# a406-4069-overdrive.net
KiCad netlist of a schematic drawn in EAGLE
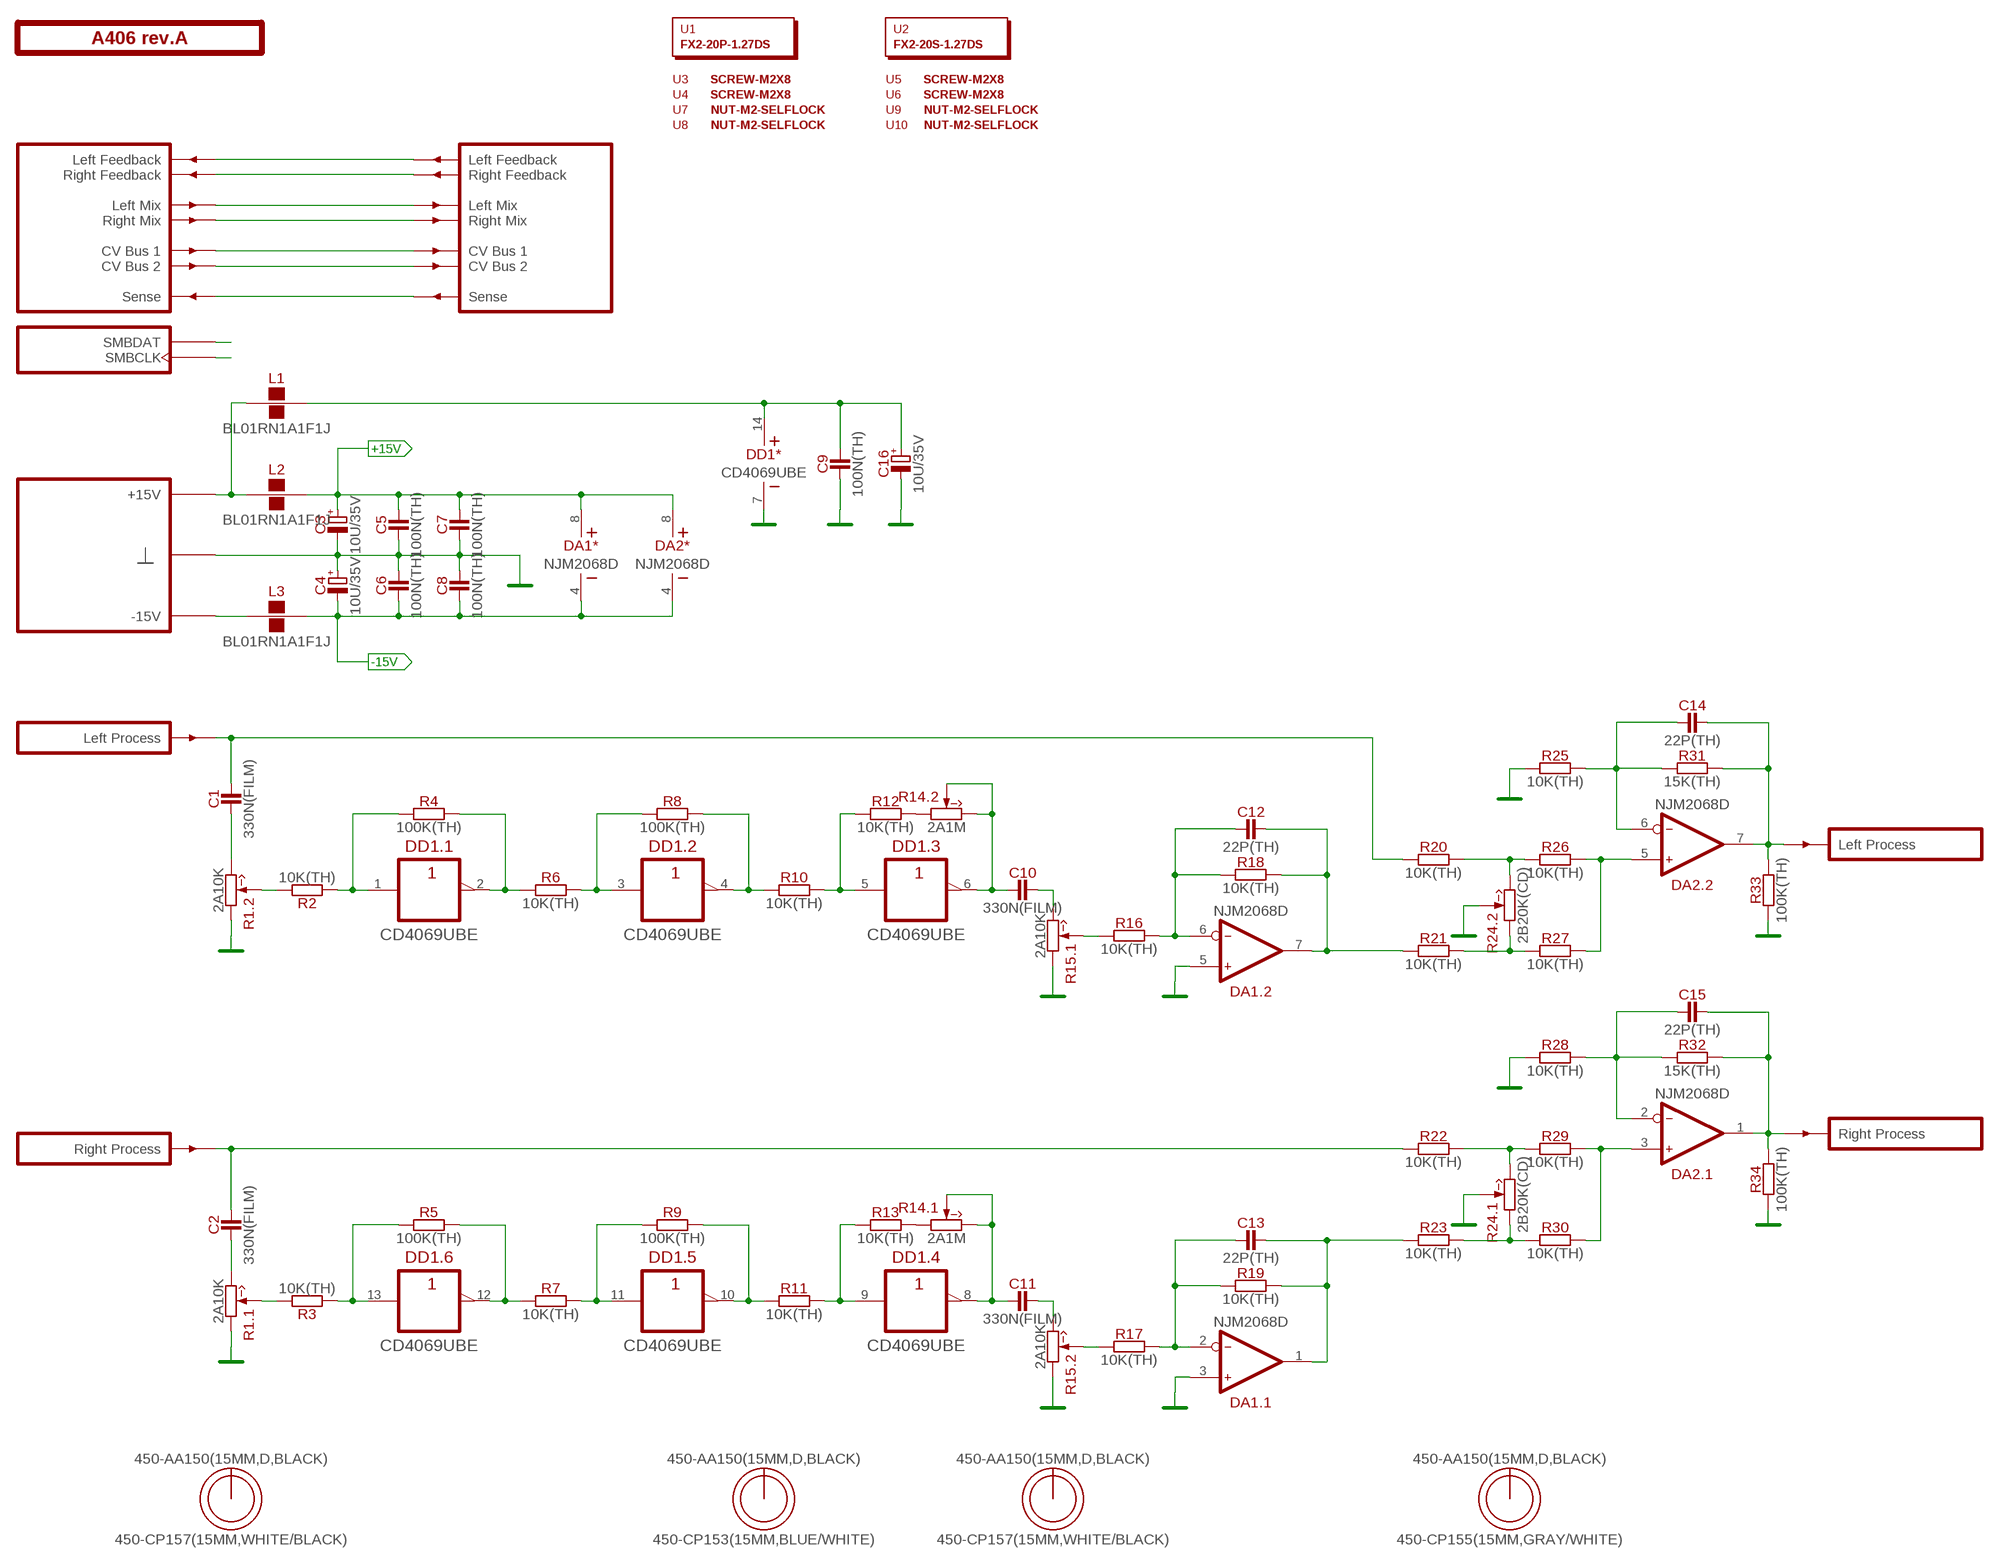
[diagram p0: schematic, sheet 1]

(export (version "E")
  (design (tool "Eeschema 10.0.6"))
  (components
    (comp (ref "C1")
      (value "330N(FILM)")
      (footprint "eagle-import:C050-035X075")
      (libsource (lib "eagle-import") (part "?330N(FILM)"))
    )
    (comp (ref "C2")
      (value "330N(FILM)")
      (footprint "eagle-import:C050-035X075")
      (libsource (lib "eagle-import") (part "?330N(FILM)"))
    )
    (comp (ref "C3")
      (value "10U/35V")
      (footprint "eagle-import:E2-5")
      (libsource (lib "eagle-import") (part "?10U/35V"))
    )
    (comp (ref "C4")
      (value "10U/35V")
      (footprint "eagle-import:E2-5")
      (libsource (lib "eagle-import") (part "?10U/35V"))
    )
    (comp (ref "C5")
      (value "100N(TH)")
      (footprint "eagle-import:C050-024X044")
      (libsource (lib "eagle-import") (part "?100N(TH)"))
    )
    (comp (ref "C6")
      (value "100N(TH)")
      (footprint "eagle-import:C050-024X044")
      (libsource (lib "eagle-import") (part "?100N(TH)"))
    )
    (comp (ref "C7")
      (value "100N(TH)")
      (footprint "eagle-import:C050-024X044")
      (libsource (lib "eagle-import") (part "?100N(TH)"))
    )
    (comp (ref "C8")
      (value "100N(TH)")
      (footprint "eagle-import:C050-024X044")
      (libsource (lib "eagle-import") (part "?100N(TH)"))
    )
    (comp (ref "C9")
      (value "100N(TH)")
      (footprint "eagle-import:C050-024X044")
      (libsource (lib "eagle-import") (part "?100N(TH)"))
    )
    (comp (ref "C10")
      (value "330N(FILM)")
      (footprint "eagle-import:C050-035X075")
      (libsource (lib "eagle-import") (part "?330N(FILM)"))
    )
    (comp (ref "C11")
      (value "330N(FILM)")
      (footprint "eagle-import:C050-035X075")
      (libsource (lib "eagle-import") (part "?330N(FILM)"))
    )
    (comp (ref "C12")
      (value "22P(TH)")
      (footprint "eagle-import:C050-024X044")
      (libsource (lib "eagle-import") (part "?22P(TH)"))
    )
    (comp (ref "C13")
      (value "22P(TH)")
      (footprint "eagle-import:C050-024X044")
      (libsource (lib "eagle-import") (part "?22P(TH)"))
    )
    (comp (ref "C14")
      (value "22P(TH)")
      (footprint "eagle-import:C050-024X044")
      (libsource (lib "eagle-import") (part "?22P(TH)"))
    )
    (comp (ref "C15")
      (value "22P(TH)")
      (footprint "eagle-import:C050-024X044")
      (libsource (lib "eagle-import") (part "?22P(TH)"))
    )
    (comp (ref "C16")
      (value "10U/35V")
      (footprint "eagle-import:E2-5")
      (libsource (lib "eagle-import") (part "?10U/35V"))
    )
    (comp (ref "DA1")
      (value "NJM2068D")
      (footprint "eagle-import:DIP-8")
      (libsource (lib "eagle-import") (part "NJM2068D"))
    )
    (comp (ref "DA2")
      (value "NJM2068D")
      (footprint "eagle-import:DIP-8")
      (libsource (lib "eagle-import") (part "NJM2068D"))
    )
    (comp (ref "DD1")
      (value "CD4069UBE")
      (footprint "eagle-import:DIP-14")
      (libsource (lib "eagle-import") (part "CD4069UBE"))
    )
    (comp (ref "L1")
      (value "BL01RN1A1F1J")
      (footprint "eagle-import:BL01RN1A")
      (libsource (lib "eagle-import") (part "BL01RN1A?1F1J"))
    )
    (comp (ref "L2")
      (value "BL01RN1A1F1J")
      (footprint "eagle-import:BL01RN1A")
      (libsource (lib "eagle-import") (part "BL01RN1A?1F1J"))
    )
    (comp (ref "L3")
      (value "BL01RN1A1F1J")
      (footprint "eagle-import:BL01RN1A")
      (libsource (lib "eagle-import") (part "BL01RN1A?1F1J"))
    )
    (comp (ref "O2")
      (value "450-AA150(15MM,D,BLACK)")
      (footprint "eagle-import:EMPTY")
      (libsource (lib "eagle-import") (part "450-AA?150(15MM,D,BLACK)"))
    )
    (comp (ref "O3")
      (value "450-CP157(15MM,WHITE/BLACK)")
      (footprint "eagle-import:EMPTY")
      (libsource (lib "eagle-import") (part "450-C?P157(15MM,WHITE/BLACK)"))
    )
    (comp (ref "O4")
      (value "450-AA150(15MM,D,BLACK)")
      (footprint "eagle-import:EMPTY")
      (libsource (lib "eagle-import") (part "450-AA?150(15MM,D,BLACK)"))
    )
    (comp (ref "O5")
      (value "450-CP153(15MM,BLUE/WHITE)")
      (footprint "eagle-import:EMPTY")
      (libsource (lib "eagle-import") (part "450-C?P153(15MM,BLUE/WHITE)"))
    )
    (comp (ref "O6")
      (value "450-AA150(15MM,D,BLACK)")
      (footprint "eagle-import:EMPTY")
      (libsource (lib "eagle-import") (part "450-AA?150(15MM,D,BLACK)"))
    )
    (comp (ref "O7")
      (value "450-CP157(15MM,WHITE/BLACK)")
      (footprint "eagle-import:EMPTY")
      (libsource (lib "eagle-import") (part "450-C?P157(15MM,WHITE/BLACK)"))
    )
    (comp (ref "O8")
      (value "450-AA150(15MM,D,BLACK)")
      (footprint "eagle-import:EMPTY")
      (libsource (lib "eagle-import") (part "450-AA?150(15MM,D,BLACK)"))
    )
    (comp (ref "O9")
      (value "450-CP155(15MM,GRAY/WHITE)")
      (footprint "eagle-import:EMPTY")
      (libsource (lib "eagle-import") (part "450-C?P155(15MM,GRAY/WHITE)"))
    )
    (comp (ref "PCB1")
      (value "A406 rev.A")
      (footprint "eagle-import:ST2-BOARD-50")
      (libsource (lib "eagle-import") (part "ST2-BOARD-?50"))
    )
    (comp (ref "R1")
      (value "2A10K")
      (footprint "eagle-import:RV11-DUAL")
      (libsource (lib "eagle-import") (part "2?A10K"))
    )
    (comp (ref "R2")
      (value "10K(TH)")
      (footprint "eagle-import:R-0207_10")
      (libsource (lib "eagle-import") (part "?10K(TH)"))
    )
    (comp (ref "R3")
      (value "10K(TH)")
      (footprint "eagle-import:R-0207_10")
      (libsource (lib "eagle-import") (part "?10K(TH)"))
    )
    (comp (ref "R4")
      (value "100K(TH)")
      (footprint "eagle-import:R-0207_10")
      (libsource (lib "eagle-import") (part "?100K(TH)"))
    )
    (comp (ref "R5")
      (value "100K(TH)")
      (footprint "eagle-import:R-0207_10")
      (libsource (lib "eagle-import") (part "?100K(TH)"))
    )
    (comp (ref "R6")
      (value "10K(TH)")
      (footprint "eagle-import:R-0207_10")
      (libsource (lib "eagle-import") (part "?10K(TH)"))
    )
    (comp (ref "R7")
      (value "10K(TH)")
      (footprint "eagle-import:R-0207_10")
      (libsource (lib "eagle-import") (part "?10K(TH)"))
    )
    (comp (ref "R8")
      (value "100K(TH)")
      (footprint "eagle-import:R-0207_10")
      (libsource (lib "eagle-import") (part "?100K(TH)"))
    )
    (comp (ref "R9")
      (value "100K(TH)")
      (footprint "eagle-import:R-0207_10")
      (libsource (lib "eagle-import") (part "?100K(TH)"))
    )
    (comp (ref "R10")
      (value "10K(TH)")
      (footprint "eagle-import:R-0207_10")
      (libsource (lib "eagle-import") (part "?10K(TH)"))
    )
    (comp (ref "R11")
      (value "10K(TH)")
      (footprint "eagle-import:R-0207_10")
      (libsource (lib "eagle-import") (part "?10K(TH)"))
    )
    (comp (ref "R12")
      (value "10K(TH)")
      (footprint "eagle-import:R-0207_10")
      (libsource (lib "eagle-import") (part "?10K(TH)"))
    )
    (comp (ref "R13")
      (value "10K(TH)")
      (footprint "eagle-import:R-0207_10")
      (libsource (lib "eagle-import") (part "?10K(TH)"))
    )
    (comp (ref "R14")
      (value "2A1M")
      (footprint "eagle-import:RV11-DUAL")
      (libsource (lib "eagle-import") (part "2?A1M"))
    )
    (comp (ref "R15")
      (value "2A10K")
      (footprint "eagle-import:RV11-DUAL")
      (libsource (lib "eagle-import") (part "2?A10K"))
    )
    (comp (ref "R16")
      (value "10K(TH)")
      (footprint "eagle-import:R-0207_10")
      (libsource (lib "eagle-import") (part "?10K(TH)"))
    )
    (comp (ref "R17")
      (value "10K(TH)")
      (footprint "eagle-import:R-0207_10")
      (libsource (lib "eagle-import") (part "?10K(TH)"))
    )
    (comp (ref "R18")
      (value "10K(TH)")
      (footprint "eagle-import:R-0207_10")
      (libsource (lib "eagle-import") (part "?10K(TH)"))
    )
    (comp (ref "R19")
      (value "10K(TH)")
      (footprint "eagle-import:R-0207_10")
      (libsource (lib "eagle-import") (part "?10K(TH)"))
    )
    (comp (ref "R20")
      (value "10K(TH)")
      (footprint "eagle-import:R-0207_10")
      (libsource (lib "eagle-import") (part "?10K(TH)"))
    )
    (comp (ref "R21")
      (value "10K(TH)")
      (footprint "eagle-import:R-0207_10")
      (libsource (lib "eagle-import") (part "?10K(TH)"))
    )
    (comp (ref "R22")
      (value "10K(TH)")
      (footprint "eagle-import:R-0207_10")
      (libsource (lib "eagle-import") (part "?10K(TH)"))
    )
    (comp (ref "R23")
      (value "10K(TH)")
      (footprint "eagle-import:R-0207_10")
      (libsource (lib "eagle-import") (part "?10K(TH)"))
    )
    (comp (ref "R24")
      (value "2B20K(CD)")
      (footprint "eagle-import:RV11-DUAL")
      (libsource (lib "eagle-import") (part "2?B20K(CD)"))
    )
    (comp (ref "R25")
      (value "10K(TH)")
      (footprint "eagle-import:R-0207_10")
      (libsource (lib "eagle-import") (part "?10K(TH)"))
    )
    (comp (ref "R26")
      (value "10K(TH)")
      (footprint "eagle-import:R-0207_10")
      (libsource (lib "eagle-import") (part "?10K(TH)"))
    )
    (comp (ref "R27")
      (value "10K(TH)")
      (footprint "eagle-import:R-0207_10")
      (libsource (lib "eagle-import") (part "?10K(TH)"))
    )
    (comp (ref "R28")
      (value "10K(TH)")
      (footprint "eagle-import:R-0207_10")
      (libsource (lib "eagle-import") (part "?10K(TH)"))
    )
    (comp (ref "R29")
      (value "10K(TH)")
      (footprint "eagle-import:R-0207_10")
      (libsource (lib "eagle-import") (part "?10K(TH)"))
    )
    (comp (ref "R30")
      (value "10K(TH)")
      (footprint "eagle-import:R-0207_10")
      (libsource (lib "eagle-import") (part "?10K(TH)"))
    )
    (comp (ref "R31")
      (value "15K(TH)")
      (footprint "eagle-import:R-0207_10")
      (libsource (lib "eagle-import") (part "?15K(TH)"))
    )
    (comp (ref "R32")
      (value "15K(TH)")
      (footprint "eagle-import:R-0207_10")
      (libsource (lib "eagle-import") (part "?15K(TH)"))
    )
    (comp (ref "R33")
      (value "100K(TH)")
      (footprint "eagle-import:R-0207_10")
      (libsource (lib "eagle-import") (part "?100K(TH)"))
    )
    (comp (ref "R34")
      (value "100K(TH)")
      (footprint "eagle-import:R-0207_10")
      (libsource (lib "eagle-import") (part "?100K(TH)"))
    )
    (comp (ref "U1")
      (value "FX2-20P-1.27DS")
      (footprint "eagle-import:EMPTY")
      (libsource (lib "eagle-import") (part "?FX2-20P-1.27DS"))
    )
    (comp (ref "U2")
      (value "FX2-20S-1.27DS")
      (footprint "eagle-import:EMPTY")
      (libsource (lib "eagle-import") (part "?FX2-20S-1.27DS"))
    )
    (comp (ref "U3")
      (value "SCREW-M2X8")
      (footprint "eagle-import:EMPTY")
      (libsource (lib "eagle-import") (part "?SCREW-M2X8"))
    )
    (comp (ref "U4")
      (value "SCREW-M2X8")
      (footprint "eagle-import:EMPTY")
      (libsource (lib "eagle-import") (part "?SCREW-M2X8"))
    )
    (comp (ref "U5")
      (value "SCREW-M2X8")
      (footprint "eagle-import:EMPTY")
      (libsource (lib "eagle-import") (part "?SCREW-M2X8"))
    )
    (comp (ref "U6")
      (value "SCREW-M2X8")
      (footprint "eagle-import:EMPTY")
      (libsource (lib "eagle-import") (part "?SCREW-M2X8"))
    )
    (comp (ref "U7")
      (value "NUT-M2-SELFLOCK")
      (footprint "eagle-import:EMPTY")
      (libsource (lib "eagle-import") (part "?NUT-M2-SELFLOCK"))
    )
    (comp (ref "U8")
      (value "NUT-M2-SELFLOCK")
      (footprint "eagle-import:EMPTY")
      (libsource (lib "eagle-import") (part "?NUT-M2-SELFLOCK"))
    )
    (comp (ref "U9")
      (value "NUT-M2-SELFLOCK")
      (footprint "eagle-import:EMPTY")
      (libsource (lib "eagle-import") (part "?NUT-M2-SELFLOCK"))
    )
    (comp (ref "U10")
      (value "NUT-M2-SELFLOCK")
      (footprint "eagle-import:EMPTY")
      (libsource (lib "eagle-import") (part "?NUT-M2-SELFLOCK"))
    )
  )
  (nets
    (net (code "1") (name "+15V") (class "Default")
      (node (ref "C3") (pin "+") (pinfunction "+_+") (pintype "passive"))
      (node (ref "C5") (pin "2") (pinfunction "2_2") (pintype "passive"))
      (node (ref "C7") (pin "2") (pinfunction "2_2") (pintype "passive"))
      (node (ref "DA1") (pin "8") (pinfunction "V+_8") (pintype "power_in"))
      (node (ref "DA2") (pin "8") (pinfunction "V+_8") (pintype "power_in"))
      (node (ref "L2") (pin "2") (pinfunction "2_2") (pintype "passive"))
    )
    (net (code "2") (name "-15V") (class "Default")
      (node (ref "C4") (pin "-") (pinfunction "-_-") (pintype "passive"))
      (node (ref "C6") (pin "1") (pinfunction "1_1") (pintype "passive"))
      (node (ref "C8") (pin "1") (pinfunction "1_1") (pintype "passive"))
      (node (ref "DA1") (pin "4") (pinfunction "V-_4") (pintype "power_in"))
      (node (ref "DA2") (pin "4") (pinfunction "V-_4") (pintype "power_in"))
      (node (ref "L3") (pin "2") (pinfunction "2_2") (pintype "passive"))
    )
    (net (code "3") (name "GND") (class "Default")
      (node (ref "C16") (pin "-") (pinfunction "-_-") (pintype "passive"))
      (node (ref "C3") (pin "-") (pinfunction "-_-") (pintype "passive"))
      (node (ref "C4") (pin "+") (pinfunction "+_+") (pintype "passive"))
      (node (ref "C5") (pin "1") (pinfunction "1_1") (pintype "passive"))
      (node (ref "C6") (pin "2") (pinfunction "2_2") (pintype "passive"))
      (node (ref "C7") (pin "1") (pinfunction "1_1") (pintype "passive"))
      (node (ref "C8") (pin "2") (pinfunction "2_2") (pintype "passive"))
      (node (ref "C9") (pin "1") (pinfunction "1_1") (pintype "passive"))
      (node (ref "DA1") (pin "3") (pinfunction "IN+_3") (pintype "input"))
      (node (ref "DA1") (pin "5") (pinfunction "IN+_5") (pintype "input"))
      (node (ref "DD1") (pin "7") (pinfunction "V-_7") (pintype "power_in"))
      (node (ref "PCB1") (pin "B4") (pinfunction "GND_B4") (pintype "bidirectional"))
      (node (ref "PCB1") (pin "B4'") (pinfunction "GND_B4'") (pintype "bidirectional"))
      (node (ref "PCB1") (pin "B5") (pinfunction "GND_B5") (pintype "bidirectional"))
      (node (ref "PCB1") (pin "B5'") (pinfunction "GND_B5'") (pintype "bidirectional"))
      (node (ref "PCB1") (pin "B6") (pinfunction "GND_B6") (pintype "bidirectional"))
      (node (ref "PCB1") (pin "B6'") (pinfunction "GND_B6'") (pintype "bidirectional"))
      (node (ref "PCB1") (pin "B7") (pinfunction "GND_B7") (pintype "bidirectional"))
      (node (ref "PCB1") (pin "B7'") (pinfunction "GND_B7'") (pintype "bidirectional"))
      (node (ref "PCB1") (pin "B8") (pinfunction "GND_B8") (pintype "bidirectional"))
      (node (ref "PCB1") (pin "B8'") (pinfunction "GND_B8'") (pintype "bidirectional"))
      (node (ref "R1") (pin "1") (pinfunction "CCW_1") (pintype "passive"))
      (node (ref "R1") (pin "1'") (pinfunction "CCW_1'") (pintype "passive"))
      (node (ref "R15") (pin "1") (pinfunction "CCW_1") (pintype "passive"))
      (node (ref "R15") (pin "1'") (pinfunction "CCW_1'") (pintype "passive"))
      (node (ref "R24") (pin "2") (pinfunction "W_2") (pintype "passive"))
      (node (ref "R24") (pin "2'") (pinfunction "W_2'") (pintype "passive"))
      (node (ref "R25") (pin "1") (pinfunction "1_1") (pintype "passive"))
      (node (ref "R28") (pin "1") (pinfunction "1_1") (pintype "passive"))
      (node (ref "R33") (pin "1") (pinfunction "1_1") (pintype "passive"))
      (node (ref "R34") (pin "1") (pinfunction "1_1") (pintype "passive"))
    )
    (net (code "4") (name "Net-(DA1B-IN-)") (class "Default")
      (node (ref "C13") (pin "1") (pinfunction "1_1") (pintype "passive"))
      (node (ref "DA1") (pin "2") (pinfunction "IN-_2") (pintype "input"))
      (node (ref "R17") (pin "2") (pinfunction "2_2") (pintype "passive"))
      (node (ref "R19") (pin "1") (pinfunction "1_1") (pintype "passive"))
    )
    (net (code "5") (name "Net-(DA1B-OUT)") (class "Default")
      (node (ref "C13") (pin "2") (pinfunction "2_2") (pintype "passive"))
      (node (ref "DA1") (pin "1") (pinfunction "OUT_1") (pintype "output"))
      (node (ref "R19") (pin "2") (pinfunction "2_2") (pintype "passive"))
      (node (ref "R23") (pin "1") (pinfunction "1_1") (pintype "passive"))
    )
    (net (code "6") (name "Net-(DA1C-IN-)") (class "Default")
      (node (ref "C12") (pin "1") (pinfunction "1_1") (pintype "passive"))
      (node (ref "DA1") (pin "6") (pinfunction "IN-_6") (pintype "input"))
      (node (ref "R16") (pin "2") (pinfunction "2_2") (pintype "passive"))
      (node (ref "R18") (pin "1") (pinfunction "1_1") (pintype "passive"))
    )
    (net (code "7") (name "Net-(DA1C-OUT)") (class "Default")
      (node (ref "C12") (pin "2") (pinfunction "2_2") (pintype "passive"))
      (node (ref "DA1") (pin "7") (pinfunction "OUT_7") (pintype "output"))
      (node (ref "R18") (pin "2") (pinfunction "2_2") (pintype "passive"))
      (node (ref "R21") (pin "1") (pinfunction "1_1") (pintype "passive"))
    )
    (net (code "8") (name "Net-(DA2B-IN+)") (class "Default")
      (node (ref "DA2") (pin "3") (pinfunction "IN+_3") (pintype "input"))
      (node (ref "R29") (pin "2") (pinfunction "2_2") (pintype "passive"))
      (node (ref "R30") (pin "2") (pinfunction "2_2") (pintype "passive"))
    )
    (net (code "9") (name "Net-(DA2B-IN-)") (class "Default")
      (node (ref "C15") (pin "1") (pinfunction "1_1") (pintype "passive"))
      (node (ref "DA2") (pin "2") (pinfunction "IN-_2") (pintype "input"))
      (node (ref "R28") (pin "2") (pinfunction "2_2") (pintype "passive"))
      (node (ref "R32") (pin "1") (pinfunction "1_1") (pintype "passive"))
    )
    (net (code "10") (name "Net-(DA2B-OUT)") (class "Default")
      (node (ref "C15") (pin "2") (pinfunction "2_2") (pintype "passive"))
      (node (ref "DA2") (pin "1") (pinfunction "OUT_1") (pintype "output"))
      (node (ref "PCB1") (pin "BOUTR'") (pinfunction "OUTR_BOUTR'") (pintype "bidirectional"))
      (node (ref "R32") (pin "2") (pinfunction "2_2") (pintype "passive"))
      (node (ref "R34") (pin "2") (pinfunction "2_2") (pintype "passive"))
    )
    (net (code "11") (name "Net-(DA2C-IN+)") (class "Default")
      (node (ref "DA2") (pin "5") (pinfunction "IN+_5") (pintype "input"))
      (node (ref "R26") (pin "2") (pinfunction "2_2") (pintype "passive"))
      (node (ref "R27") (pin "2") (pinfunction "2_2") (pintype "passive"))
    )
    (net (code "12") (name "Net-(DA2C-IN-)") (class "Default")
      (node (ref "C14") (pin "1") (pinfunction "1_1") (pintype "passive"))
      (node (ref "DA2") (pin "6") (pinfunction "IN-_6") (pintype "input"))
      (node (ref "R25") (pin "2") (pinfunction "2_2") (pintype "passive"))
      (node (ref "R31") (pin "1") (pinfunction "1_1") (pintype "passive"))
    )
    (net (code "13") (name "Net-(DA2C-OUT)") (class "Default")
      (node (ref "C14") (pin "2") (pinfunction "2_2") (pintype "passive"))
      (node (ref "DA2") (pin "7") (pinfunction "OUT_7") (pintype "output"))
      (node (ref "PCB1") (pin "BOUTL'") (pinfunction "OUTL_BOUTL'") (pintype "bidirectional"))
      (node (ref "R31") (pin "2") (pinfunction "2_2") (pintype "passive"))
      (node (ref "R33") (pin "2") (pinfunction "2_2") (pintype "passive"))
    )
    (net (code "14") (name "Net-(DD1A-V+)") (class "Default")
      (node (ref "C16") (pin "+") (pinfunction "+_+") (pintype "passive"))
      (node (ref "C9") (pin "2") (pinfunction "2_2") (pintype "passive"))
      (node (ref "DD1") (pin "14") (pinfunction "V+_14") (pintype "power_in"))
      (node (ref "L1") (pin "2") (pinfunction "2_2") (pintype "passive"))
    )
    (net (code "15") (name "Net-(DD1B-A)") (class "Default")
      (node (ref "DD1") (pin "1") (pinfunction "A_1") (pintype "input"))
      (node (ref "R2") (pin "1") (pinfunction "1_1") (pintype "passive"))
      (node (ref "R4") (pin "1") (pinfunction "1_1") (pintype "passive"))
    )
    (net (code "16") (name "Net-(DD1B-Y)") (class "Default")
      (node (ref "DD1") (pin "2") (pinfunction "Y_2") (pintype "output"))
      (node (ref "R4") (pin "2") (pinfunction "2_2") (pintype "passive"))
      (node (ref "R6") (pin "1") (pinfunction "1_1") (pintype "passive"))
    )
    (net (code "17") (name "Net-(DD1C-A)") (class "Default")
      (node (ref "DD1") (pin "3") (pinfunction "A_3") (pintype "input"))
      (node (ref "R6") (pin "2") (pinfunction "2_2") (pintype "passive"))
      (node (ref "R8") (pin "1") (pinfunction "1_1") (pintype "passive"))
    )
    (net (code "18") (name "Net-(DD1C-Y)") (class "Default")
      (node (ref "DD1") (pin "4") (pinfunction "Y_4") (pintype "output"))
      (node (ref "R10") (pin "1") (pinfunction "1_1") (pintype "passive"))
      (node (ref "R8") (pin "2") (pinfunction "2_2") (pintype "passive"))
    )
    (net (code "19") (name "Net-(DD1D-A)") (class "Default")
      (node (ref "DD1") (pin "5") (pinfunction "A_5") (pintype "input"))
      (node (ref "R10") (pin "2") (pinfunction "2_2") (pintype "passive"))
      (node (ref "R12") (pin "1") (pinfunction "1_1") (pintype "passive"))
    )
    (net (code "20") (name "Net-(DD1D-Y)") (class "Default")
      (node (ref "C10") (pin "1") (pinfunction "1_1") (pintype "passive"))
      (node (ref "DD1") (pin "6") (pinfunction "Y_6") (pintype "output"))
      (node (ref "R14") (pin "2'") (pinfunction "W_2'") (pintype "passive"))
      (node (ref "R14") (pin "3'") (pinfunction "CW_3'") (pintype "passive"))
    )
    (net (code "21") (name "Net-(DD1E-A)") (class "Default")
      (node (ref "DD1") (pin "9") (pinfunction "A_9") (pintype "input"))
      (node (ref "R11") (pin "2") (pinfunction "2_2") (pintype "passive"))
      (node (ref "R13") (pin "1") (pinfunction "1_1") (pintype "passive"))
    )
    (net (code "22") (name "Net-(DD1E-Y)") (class "Default")
      (node (ref "C11") (pin "1") (pinfunction "1_1") (pintype "passive"))
      (node (ref "DD1") (pin "8") (pinfunction "Y_8") (pintype "output"))
      (node (ref "R14") (pin "2") (pinfunction "W_2") (pintype "passive"))
      (node (ref "R14") (pin "3") (pinfunction "CW_3") (pintype "passive"))
    )
    (net (code "23") (name "Net-(DD1F-A)") (class "Default")
      (node (ref "DD1") (pin "11") (pinfunction "A_11") (pintype "input"))
      (node (ref "R7") (pin "2") (pinfunction "2_2") (pintype "passive"))
      (node (ref "R9") (pin "1") (pinfunction "1_1") (pintype "passive"))
    )
    (net (code "24") (name "Net-(DD1F-Y)") (class "Default")
      (node (ref "DD1") (pin "10") (pinfunction "Y_10") (pintype "output"))
      (node (ref "R11") (pin "1") (pinfunction "1_1") (pintype "passive"))
      (node (ref "R9") (pin "2") (pinfunction "2_2") (pintype "passive"))
    )
    (net (code "25") (name "Net-(DD1G-A)") (class "Default")
      (node (ref "DD1") (pin "13") (pinfunction "A_13") (pintype "input"))
      (node (ref "R3") (pin "1") (pinfunction "1_1") (pintype "passive"))
      (node (ref "R5") (pin "1") (pinfunction "1_1") (pintype "passive"))
    )
    (net (code "26") (name "Net-(DD1G-Y)") (class "Default")
      (node (ref "DD1") (pin "12") (pinfunction "Y_12") (pintype "output"))
      (node (ref "R5") (pin "2") (pinfunction "2_2") (pintype "passive"))
      (node (ref "R7") (pin "1") (pinfunction "1_1") (pintype "passive"))
    )
    (net (code "27") (name "Net-(L1-Pad1)") (class "Default")
      (node (ref "L1") (pin "1") (pinfunction "1_1") (pintype "passive"))
      (node (ref "L2") (pin "1") (pinfunction "1_1") (pintype "passive"))
      (node (ref "PCB1") (pin "A+15") (pinfunction "P+15V_A+15") (pintype "bidirectional"))
      (node (ref "PCB1") (pin "A+15'") (pinfunction "P+15V_A+15'") (pintype "bidirectional"))
      (node (ref "PCB1") (pin "B+15") (pinfunction "P+15V_B+15") (pintype "bidirectional"))
      (node (ref "PCB1") (pin "B+15'") (pinfunction "P+15V_B+15'") (pintype "bidirectional"))
    )
    (net (code "28") (name "Net-(L3-Pad1)") (class "Default")
      (node (ref "L3") (pin "1") (pinfunction "1_1") (pintype "passive"))
      (node (ref "PCB1") (pin "A-15") (pinfunction "P-15V_A-15") (pintype "bidirectional"))
      (node (ref "PCB1") (pin "A-15'") (pinfunction "P-15V_A-15'") (pintype "bidirectional"))
      (node (ref "PCB1") (pin "B-15") (pinfunction "P-15V_B-15") (pintype "bidirectional"))
      (node (ref "PCB1") (pin "B-15'") (pinfunction "P-15V_B-15'") (pintype "bidirectional"))
    )
    (net (code "29") (name "Net-(PCB1B-INL)") (class "Default")
      (node (ref "C1") (pin "2") (pinfunction "2_2") (pintype "passive"))
      (node (ref "PCB1") (pin "BINL") (pinfunction "INL_BINL") (pintype "bidirectional"))
      (node (ref "R20") (pin "1") (pinfunction "1_1") (pintype "passive"))
    )
    (net (code "30") (name "Net-(PCB1C-INR)") (class "Default")
      (node (ref "C2") (pin "2") (pinfunction "2_2") (pintype "passive"))
      (node (ref "PCB1") (pin "BINR") (pinfunction "INR_BINR") (pintype "bidirectional"))
      (node (ref "R22") (pin "1") (pinfunction "1_1") (pintype "passive"))
    )
    (net (code "31") (name "Net-(PCB1F-CV1)") (class "Default")
      (node (ref "PCB1") (pin "ACV1") (pinfunction "CV1_ACV1") (pintype "bidirectional"))
      (node (ref "PCB1") (pin "ACV1'") (pinfunction "CV1'_ACV1'") (pintype "bidirectional"))
    )
    (net (code "32") (name "Net-(PCB1F-CV2)") (class "Default")
      (node (ref "PCB1") (pin "ACV2") (pinfunction "CV2_ACV2") (pintype "bidirectional"))
      (node (ref "PCB1") (pin "ACV2'") (pinfunction "CV2'_ACV2'") (pintype "bidirectional"))
    )
    (net (code "33") (name "Net-(PCB1F-LFBK)") (class "Default")
      (node (ref "PCB1") (pin "ALFBK") (pinfunction "LFBK_ALFBK") (pintype "bidirectional"))
      (node (ref "PCB1") (pin "ALFBK'") (pinfunction "LFBK'_ALFBK'") (pintype "bidirectional"))
    )
    (net (code "34") (name "Net-(PCB1F-LMIX)") (class "Default")
      (node (ref "PCB1") (pin "ALMIX") (pinfunction "LMIX_ALMIX") (pintype "bidirectional"))
      (node (ref "PCB1") (pin "ALMIX'") (pinfunction "LMIX'_ALMIX'") (pintype "bidirectional"))
    )
    (net (code "35") (name "Net-(PCB1F-RFBK)") (class "Default")
      (node (ref "PCB1") (pin "ARFBK") (pinfunction "RFBK_ARFBK") (pintype "bidirectional"))
      (node (ref "PCB1") (pin "ARFBK'") (pinfunction "RFBK'_ARFBK'") (pintype "bidirectional"))
    )
    (net (code "36") (name "Net-(PCB1F-RMIX)") (class "Default")
      (node (ref "PCB1") (pin "ARMIX") (pinfunction "RMIX_ARMIX") (pintype "bidirectional"))
      (node (ref "PCB1") (pin "ARMIX'") (pinfunction "RMIX'_ARMIX'") (pintype "bidirectional"))
    )
    (net (code "37") (name "Net-(PCB1F-SENSE)") (class "Default")
      (node (ref "PCB1") (pin "BSENSE") (pinfunction "SENSE_BSENSE") (pintype "bidirectional"))
      (node (ref "PCB1") (pin "BSENSE'") (pinfunction "SENSE'_BSENSE'") (pintype "bidirectional"))
    )
    (net (code "38") (name "Net-(PCB1H-SMBCLK-PadASMBCLK')") (class "Default")
      (node (ref "PCB1") (pin "ASMBCLK") (pinfunction "SMBCLK_ASMBCLK") (pintype "bidirectional"))
      (node (ref "PCB1") (pin "ASMBCLK'") (pinfunction "SMBCLK_ASMBCLK'") (pintype "bidirectional"))
    )
    (net (code "39") (name "Net-(PCB1H-SMBDAT-PadASMBDAT')") (class "Default")
      (node (ref "PCB1") (pin "ASMBDAT") (pinfunction "SMBDAT_ASMBDAT") (pintype "bidirectional"))
      (node (ref "PCB1") (pin "ASMBDAT'") (pinfunction "SMBDAT_ASMBDAT'") (pintype "bidirectional"))
    )
    (net (code "40") (name "Net-(R1A-CW)") (class "Default")
      (node (ref "C2") (pin "1") (pinfunction "1_1") (pintype "passive"))
      (node (ref "R1") (pin "3") (pinfunction "CW_3") (pintype "passive"))
    )
    (net (code "41") (name "Net-(R1A-W)") (class "Default")
      (node (ref "R1") (pin "2") (pinfunction "W_2") (pintype "passive"))
      (node (ref "R3") (pin "2") (pinfunction "2_2") (pintype "passive"))
    )
    (net (code "42") (name "Net-(R1B-CW)") (class "Default")
      (node (ref "C1") (pin "1") (pinfunction "1_1") (pintype "passive"))
      (node (ref "R1") (pin "3'") (pinfunction "CW_3'") (pintype "passive"))
    )
    (net (code "43") (name "Net-(R1B-W)") (class "Default")
      (node (ref "R1") (pin "2'") (pinfunction "W_2'") (pintype "passive"))
      (node (ref "R2") (pin "2") (pinfunction "2_2") (pintype "passive"))
    )
    (net (code "44") (name "Net-(R14A-CCW)") (class "Default")
      (node (ref "R13") (pin "2") (pinfunction "2_2") (pintype "passive"))
      (node (ref "R14") (pin "1") (pinfunction "CCW_1") (pintype "passive"))
    )
    (net (code "45") (name "Net-(R14B-CCW)") (class "Default")
      (node (ref "R12") (pin "2") (pinfunction "2_2") (pintype "passive"))
      (node (ref "R14") (pin "1'") (pinfunction "CCW_1'") (pintype "passive"))
    )
    (net (code "46") (name "Net-(R15A-CW)") (class "Default")
      (node (ref "C10") (pin "2") (pinfunction "2_2") (pintype "passive"))
      (node (ref "R15") (pin "3") (pinfunction "CW_3") (pintype "passive"))
    )
    (net (code "47") (name "Net-(R15A-W)") (class "Default")
      (node (ref "R15") (pin "2") (pinfunction "W_2") (pintype "passive"))
      (node (ref "R16") (pin "1") (pinfunction "1_1") (pintype "passive"))
    )
    (net (code "48") (name "Net-(R15B-CW)") (class "Default")
      (node (ref "C11") (pin "2") (pinfunction "2_2") (pintype "passive"))
      (node (ref "R15") (pin "3'") (pinfunction "CW_3'") (pintype "passive"))
    )
    (net (code "49") (name "Net-(R15B-W)") (class "Default")
      (node (ref "R15") (pin "2'") (pinfunction "W_2'") (pintype "passive"))
      (node (ref "R17") (pin "1") (pinfunction "1_1") (pintype "passive"))
    )
    (net (code "50") (name "Net-(R24A-CCW)") (class "Default")
      (node (ref "R23") (pin "2") (pinfunction "2_2") (pintype "passive"))
      (node (ref "R24") (pin "1") (pinfunction "CCW_1") (pintype "passive"))
      (node (ref "R30") (pin "1") (pinfunction "1_1") (pintype "passive"))
    )
    (net (code "51") (name "Net-(R24A-CW)") (class "Default")
      (node (ref "R22") (pin "2") (pinfunction "2_2") (pintype "passive"))
      (node (ref "R24") (pin "3") (pinfunction "CW_3") (pintype "passive"))
      (node (ref "R29") (pin "1") (pinfunction "1_1") (pintype "passive"))
    )
    (net (code "52") (name "Net-(R24B-CCW)") (class "Default")
      (node (ref "R21") (pin "2") (pinfunction "2_2") (pintype "passive"))
      (node (ref "R24") (pin "1'") (pinfunction "CCW_1'") (pintype "passive"))
      (node (ref "R27") (pin "1") (pinfunction "1_1") (pintype "passive"))
    )
    (net (code "53") (name "Net-(R24B-CW)") (class "Default")
      (node (ref "R20") (pin "2") (pinfunction "2_2") (pintype "passive"))
      (node (ref "R24") (pin "3'") (pinfunction "CW_3'") (pintype "passive"))
      (node (ref "R26") (pin "1") (pinfunction "1_1") (pintype "passive"))
    )
  )
)
